# Test_Board.net
KiCad netlist of a schematic drawn in Altium Designer
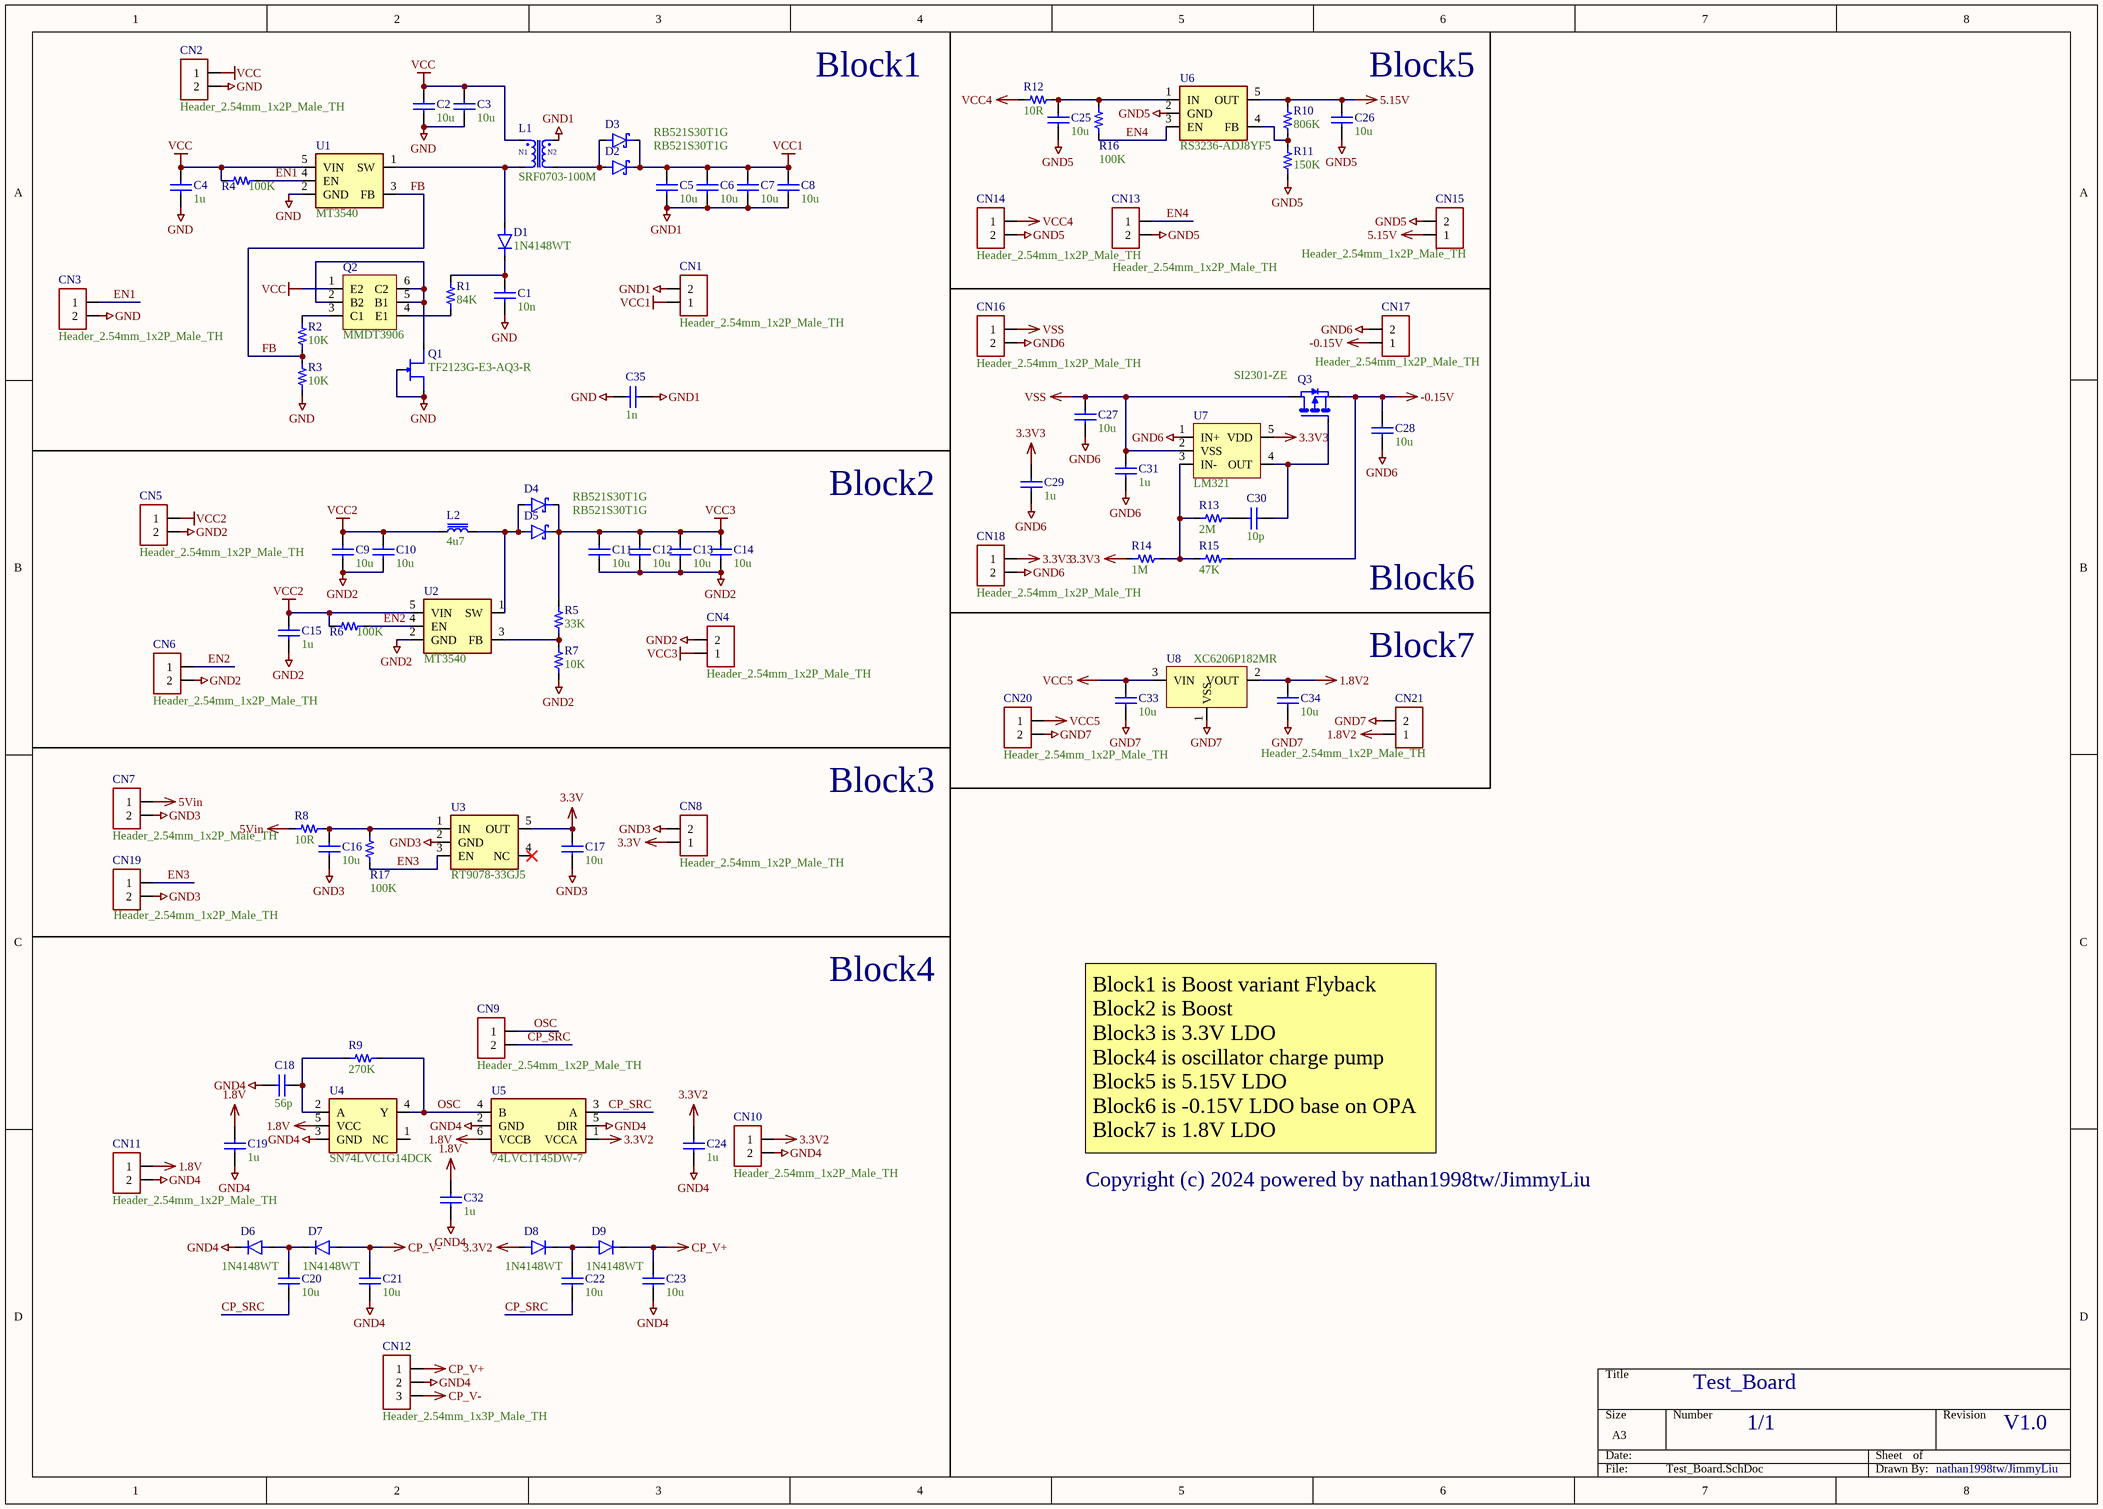
[diagram p0: Test_Board.SchDoc]

(export (version "E")
  (design (tool "Eeschema 10.0.6"))
  (components
    (comp (ref "C1")
      (value "10n")
      (footprint "CAP_0402")
      (description "Capacitor")
      (fields (field (name "VOLTAGE") "V"))
      (libsource (lib "Passive") (part "Capacitor"))
    )
    (comp (ref "C2")
      (value "10u")
      (footprint "CAP_0603")
      (description "Capacitor")
      (fields (field (name "VOLTAGE") "V"))
      (libsource (lib "Passive") (part "Capacitor"))
    )
    (comp (ref "C3")
      (value "10u")
      (footprint "CAP_0603")
      (description "Capacitor")
      (fields (field (name "VOLTAGE") "V"))
      (libsource (lib "Passive") (part "Capacitor"))
    )
    (comp (ref "C4")
      (value "1u")
      (footprint "CAP_0402")
      (description "Capacitor")
      (fields (field (name "VOLTAGE") "V"))
      (libsource (lib "Passive") (part "Capacitor"))
    )
    (comp (ref "C5")
      (value "10u")
      (footprint "CAP_0603")
      (description "Capacitor")
      (fields (field (name "VOLTAGE") "V"))
      (libsource (lib "Passive") (part "Capacitor"))
    )
    (comp (ref "C6")
      (value "10u")
      (footprint "CAP_0603")
      (description "Capacitor")
      (fields (field (name "VOLTAGE") "V"))
      (libsource (lib "Passive") (part "Capacitor"))
    )
    (comp (ref "C7")
      (value "10u")
      (footprint "CAP_0603")
      (description "Capacitor")
      (fields (field (name "VOLTAGE") "V"))
      (libsource (lib "Passive") (part "Capacitor"))
    )
    (comp (ref "C8")
      (value "10u")
      (footprint "CAP_0603")
      (description "Capacitor")
      (fields (field (name "VOLTAGE") "V"))
      (libsource (lib "Passive") (part "Capacitor"))
    )
    (comp (ref "C9")
      (value "10u")
      (footprint "CAP_0603")
      (description "Capacitor")
      (fields (field (name "VOLTAGE") "V"))
      (libsource (lib "Passive") (part "Capacitor"))
    )
    (comp (ref "C10")
      (value "10u")
      (footprint "CAP_0603")
      (description "Capacitor")
      (fields (field (name "VOLTAGE") "V"))
      (libsource (lib "Passive") (part "Capacitor"))
    )
    (comp (ref "C11")
      (value "10u")
      (footprint "CAP_0603")
      (description "Capacitor")
      (fields (field (name "VOLTAGE") "V"))
      (libsource (lib "Passive") (part "Capacitor"))
    )
    (comp (ref "C12")
      (value "10u")
      (footprint "CAP_0603")
      (description "Capacitor")
      (fields (field (name "VOLTAGE") "V"))
      (libsource (lib "Passive") (part "Capacitor"))
    )
    (comp (ref "C13")
      (value "10u")
      (footprint "CAP_0603")
      (description "Capacitor")
      (fields (field (name "VOLTAGE") "V"))
      (libsource (lib "Passive") (part "Capacitor"))
    )
    (comp (ref "C14")
      (value "10u")
      (footprint "CAP_0603")
      (description "Capacitor")
      (fields (field (name "VOLTAGE") "V"))
      (libsource (lib "Passive") (part "Capacitor"))
    )
    (comp (ref "C15")
      (value "1u")
      (footprint "CAP_0402")
      (description "Capacitor")
      (fields (field (name "VOLTAGE") "V"))
      (libsource (lib "Passive") (part "Capacitor"))
    )
    (comp (ref "C16")
      (value "10u")
      (footprint "CAP_0603")
      (description "Capacitor")
      (fields (field (name "VOLTAGE") "V"))
      (libsource (lib "Passive") (part "Capacitor"))
    )
    (comp (ref "C17")
      (value "10u")
      (footprint "CAP_0603")
      (description "Capacitor")
      (fields (field (name "VOLTAGE") "V"))
      (libsource (lib "Passive") (part "Capacitor"))
    )
    (comp (ref "C18")
      (value "56p")
      (footprint "CAP_0402")
      (description "Capacitor")
      (fields (field (name "VOLTAGE") "V"))
      (libsource (lib "Passive") (part "Capacitor"))
    )
    (comp (ref "C19")
      (value "1u")
      (footprint "CAP_0402")
      (description "Capacitor")
      (fields (field (name "VOLTAGE") "V"))
      (libsource (lib "Passive") (part "Capacitor"))
    )
    (comp (ref "C20")
      (value "10u")
      (footprint "CAP_0402")
      (description "Capacitor")
      (fields (field (name "VOLTAGE") "V"))
      (libsource (lib "Passive") (part "Capacitor"))
    )
    (comp (ref "C21")
      (value "10u")
      (footprint "CAP_0402")
      (description "Capacitor")
      (fields (field (name "VOLTAGE") "V"))
      (libsource (lib "Passive") (part "Capacitor"))
    )
    (comp (ref "C22")
      (value "10u")
      (footprint "CAP_0402")
      (description "Capacitor")
      (fields (field (name "VOLTAGE") "V"))
      (libsource (lib "Passive") (part "Capacitor"))
    )
    (comp (ref "C23")
      (value "10u")
      (footprint "CAP_0402")
      (description "Capacitor")
      (fields (field (name "VOLTAGE") "V"))
      (libsource (lib "Passive") (part "Capacitor"))
    )
    (comp (ref "C24")
      (value "1u")
      (footprint "CAP_0402")
      (description "Capacitor")
      (fields (field (name "VOLTAGE") "V"))
      (libsource (lib "Passive") (part "Capacitor"))
    )
    (comp (ref "C25")
      (value "10u")
      (footprint "CAP_0603")
      (description "Capacitor")
      (fields (field (name "VOLTAGE") "V"))
      (libsource (lib "Passive") (part "Capacitor"))
    )
    (comp (ref "C26")
      (value "10u")
      (footprint "CAP_0603")
      (description "Capacitor")
      (fields (field (name "VOLTAGE") "V"))
      (libsource (lib "Passive") (part "Capacitor"))
    )
    (comp (ref "C27")
      (value "10u")
      (footprint "CAP_0603")
      (description "Capacitor")
      (fields (field (name "VOLTAGE") "V"))
      (libsource (lib "Passive") (part "Capacitor"))
    )
    (comp (ref "C28")
      (value "10u")
      (footprint "CAP_0402")
      (description "Capacitor")
      (fields (field (name "VOLTAGE") "V"))
      (libsource (lib "Passive") (part "Capacitor"))
    )
    (comp (ref "C29")
      (value "1u")
      (footprint "CAP_0402")
      (description "Capacitor")
      (fields (field (name "VOLTAGE") "V"))
      (libsource (lib "Passive") (part "Capacitor"))
    )
    (comp (ref "C30")
      (value "10p")
      (footprint "CAP_0402")
      (description "Capacitor")
      (fields (field (name "VOLTAGE") "V"))
      (libsource (lib "Passive") (part "Capacitor"))
    )
    (comp (ref "C31")
      (value "1u")
      (footprint "CAP_0402")
      (description "Capacitor")
      (fields (field (name "VOLTAGE") "V"))
      (libsource (lib "Passive") (part "Capacitor"))
    )
    (comp (ref "C32")
      (value "1u")
      (footprint "CAP_0402")
      (description "Capacitor")
      (fields (field (name "VOLTAGE") "V"))
      (libsource (lib "Passive") (part "Capacitor"))
    )
    (comp (ref "C33")
      (value "10u")
      (footprint "CAP_0603")
      (description "Capacitor")
      (fields (field (name "VOLTAGE") "V"))
      (libsource (lib "Passive") (part "Capacitor"))
    )
    (comp (ref "C34")
      (value "10u")
      (footprint "CAP_0603")
      (description "Capacitor")
      (fields (field (name "VOLTAGE") "V"))
      (libsource (lib "Passive") (part "Capacitor"))
    )
    (comp (ref "C35")
      (value "1n")
      (footprint "CAP_0402")
      (description "Capacitor")
      (fields (field (name "VOLTAGE") "V"))
      (libsource (lib "Passive") (part "Capacitor"))
    )
    (comp (ref "CN1")
      (value "Header_2.54mm_1x2P_Male_TH")
      (footprint "Header_2.54mm_1x2P_Male_TH")
      (description "Header_2.54mm_1x2P_Male\r\nThrough-hole")
      (libsource (lib "Connector") (part "Header_2.54mm_1x2P_Male_TH"))
    )
    (comp (ref "CN2")
      (value "Header_2.54mm_1x2P_Male_TH")
      (footprint "Header_2.54mm_1x2P_Male_TH")
      (description "Header_2.54mm_1x2P_Male\r\nThrough-hole")
      (libsource (lib "Connector") (part "Header_2.54mm_1x2P_Male_TH"))
    )
    (comp (ref "CN3")
      (value "Header_2.54mm_1x2P_Male_TH")
      (footprint "Header_2.54mm_1x2P_Male_TH")
      (description "Header_2.54mm_1x2P_Male\r\nThrough-hole")
      (libsource (lib "Connector") (part "Header_2.54mm_1x2P_Male_TH"))
    )
    (comp (ref "CN4")
      (value "Header_2.54mm_1x2P_Male_TH")
      (footprint "Header_2.54mm_1x2P_Male_TH")
      (description "Header_2.54mm_1x2P_Male\r\nThrough-hole")
      (libsource (lib "Connector") (part "Header_2.54mm_1x2P_Male_TH"))
    )
    (comp (ref "CN5")
      (value "Header_2.54mm_1x2P_Male_TH")
      (footprint "Header_2.54mm_1x2P_Male_TH")
      (description "Header_2.54mm_1x2P_Male\r\nThrough-hole")
      (libsource (lib "Connector") (part "Header_2.54mm_1x2P_Male_TH"))
    )
    (comp (ref "CN6")
      (value "Header_2.54mm_1x2P_Male_TH")
      (footprint "Header_2.54mm_1x2P_Male_TH")
      (description "Header_2.54mm_1x2P_Male\r\nThrough-hole")
      (libsource (lib "Connector") (part "Header_2.54mm_1x2P_Male_TH"))
    )
    (comp (ref "CN7")
      (value "Header_2.54mm_1x2P_Male_TH")
      (footprint "Header_2.54mm_1x2P_Male_TH")
      (description "Header_2.54mm_1x2P_Male\r\nThrough-hole")
      (libsource (lib "Connector") (part "Header_2.54mm_1x2P_Male_TH"))
    )
    (comp (ref "CN8")
      (value "Header_2.54mm_1x2P_Male_TH")
      (footprint "Header_2.54mm_1x2P_Male_TH")
      (description "Header_2.54mm_1x2P_Male\r\nThrough-hole")
      (libsource (lib "Connector") (part "Header_2.54mm_1x2P_Male_TH"))
    )
    (comp (ref "CN9")
      (value "Header_2.54mm_1x2P_Male_TH")
      (footprint "Header_2.54mm_1x2P_Male_TH")
      (description "Header_2.54mm_1x2P_Male\r\nThrough-hole")
      (libsource (lib "Connector") (part "Header_2.54mm_1x2P_Male_TH"))
    )
    (comp (ref "CN10")
      (value "Header_2.54mm_1x2P_Male_TH")
      (footprint "Header_2.54mm_1x2P_Male_TH")
      (description "Header_2.54mm_1x2P_Male\r\nThrough-hole")
      (libsource (lib "Connector") (part "Header_2.54mm_1x2P_Male_TH"))
    )
    (comp (ref "CN11")
      (value "Header_2.54mm_1x2P_Male_TH")
      (footprint "Header_2.54mm_1x2P_Male_TH")
      (description "Header_2.54mm_1x2P_Male\r\nThrough-hole")
      (libsource (lib "Connector") (part "Header_2.54mm_1x2P_Male_TH"))
    )
    (comp (ref "CN12")
      (value "Header_2.54mm_1x3P_Male_TH")
      (footprint "Header_2.54mm_1x3P_Male_TH")
      (description "Header_2.54mm_1x3P_Male\r\nThrough-hole")
      (libsource (lib "Connector") (part "Header_2.54mm_1x3P_Male_TH"))
    )
    (comp (ref "CN13")
      (value "Header_2.54mm_1x2P_Male_TH")
      (footprint "Header_2.54mm_1x2P_Male_TH")
      (description "Header_2.54mm_1x2P_Male\r\nThrough-hole")
      (libsource (lib "Connector") (part "Header_2.54mm_1x2P_Male_TH"))
    )
    (comp (ref "CN14")
      (value "Header_2.54mm_1x2P_Male_TH")
      (footprint "Header_2.54mm_1x2P_Male_TH")
      (description "Header_2.54mm_1x2P_Male\r\nThrough-hole")
      (libsource (lib "Connector") (part "Header_2.54mm_1x2P_Male_TH"))
    )
    (comp (ref "CN15")
      (value "Header_2.54mm_1x2P_Male_TH")
      (footprint "Header_2.54mm_1x2P_Male_TH")
      (description "Header_2.54mm_1x2P_Male\r\nThrough-hole")
      (libsource (lib "Connector") (part "Header_2.54mm_1x2P_Male_TH"))
    )
    (comp (ref "CN16")
      (value "Header_2.54mm_1x2P_Male_TH")
      (footprint "Header_2.54mm_1x2P_Male_TH")
      (description "Header_2.54mm_1x2P_Male\r\nThrough-hole")
      (libsource (lib "Connector") (part "Header_2.54mm_1x2P_Male_TH"))
    )
    (comp (ref "CN17")
      (value "Header_2.54mm_1x2P_Male_TH")
      (footprint "Header_2.54mm_1x2P_Male_TH")
      (description "Header_2.54mm_1x2P_Male\r\nThrough-hole")
      (libsource (lib "Connector") (part "Header_2.54mm_1x2P_Male_TH"))
    )
    (comp (ref "CN18")
      (value "Header_2.54mm_1x2P_Male_TH")
      (footprint "Header_2.54mm_1x2P_Male_TH")
      (description "Header_2.54mm_1x2P_Male\r\nThrough-hole")
      (libsource (lib "Connector") (part "Header_2.54mm_1x2P_Male_TH"))
    )
    (comp (ref "CN19")
      (value "Header_2.54mm_1x2P_Male_TH")
      (footprint "Header_2.54mm_1x2P_Male_TH")
      (description "Header_2.54mm_1x2P_Male\r\nThrough-hole")
      (libsource (lib "Connector") (part "Header_2.54mm_1x2P_Male_TH"))
    )
    (comp (ref "CN20")
      (value "Header_2.54mm_1x2P_Male_TH")
      (footprint "Header_2.54mm_1x2P_Male_TH")
      (description "Header_2.54mm_1x2P_Male\r\nThrough-hole")
      (libsource (lib "Connector") (part "Header_2.54mm_1x2P_Male_TH"))
    )
    (comp (ref "CN21")
      (value "Header_2.54mm_1x2P_Male_TH")
      (footprint "Header_2.54mm_1x2P_Male_TH")
      (description "Header_2.54mm_1x2P_Male\r\nThrough-hole")
      (libsource (lib "Connector") (part "Header_2.54mm_1x2P_Male_TH"))
    )
    (comp (ref "D1")
      (value "1N4148WT")
      (footprint "SOD-523-2")
      (description "Signal Diode")
      (libsource (lib "Diode") (part "1N4148WT"))
    )
    (comp (ref "D2")
      (value "RB521S30T1G")
      (footprint "SOD-523-2")
      (description "Schottky Diode")
      (libsource (lib "Diode") (part "RB521S30T1G"))
    )
    (comp (ref "D3")
      (value "RB521S30T1G")
      (footprint "SOD-523-2")
      (description "Schottky Diode")
      (libsource (lib "Diode") (part "RB521S30T1G"))
    )
    (comp (ref "D4")
      (value "RB521S30T1G")
      (footprint "SOD-523-2")
      (description "Schottky Diode")
      (libsource (lib "Diode") (part "RB521S30T1G"))
    )
    (comp (ref "D5")
      (value "RB521S30T1G")
      (footprint "SOD-523-2")
      (description "Schottky Diode")
      (libsource (lib "Diode") (part "RB521S30T1G"))
    )
    (comp (ref "D6")
      (value "1N4148WT")
      (footprint "SOD-523-2")
      (description "Signal Diode")
      (libsource (lib "Diode") (part "1N4148WT"))
    )
    (comp (ref "D7")
      (value "1N4148WT")
      (footprint "SOD-523-2")
      (description "Signal Diode")
      (libsource (lib "Diode") (part "1N4148WT"))
    )
    (comp (ref "D8")
      (value "1N4148WT")
      (footprint "SOD-523-2")
      (description "Signal Diode")
      (libsource (lib "Diode") (part "1N4148WT"))
    )
    (comp (ref "D9")
      (value "1N4148WT")
      (footprint "SOD-523-2")
      (description "Signal Diode")
      (libsource (lib "Diode") (part "1N4148WT"))
    )
    (comp (ref "L1")
      (value "SRF0703-100M")
      (footprint "SRF0703")
      (libsource (lib "Passive") (part "SRF0703-100M"))
    )
    (comp (ref "L2")
      (value "4u7")
      (footprint "IND_0806")
      (description "Inductor_IRON")
      (libsource (lib "Passive") (part "Inductor_IRON"))
    )
    (comp (ref "Q1")
      (value "TF2123G-E3-AQ3-R")
      (footprint "SOT-723-3_120X80X50_40P")
      (description "N-JFET")
      (libsource (lib "Transistor") (part "TF2123G-E3-AQ3-R"))
    )
    (comp (ref "Q2")
      (value "MMDT3906")
      (footprint "SOT-363-6_215X130X110_65P")
      (description "Double PNP")
      (libsource (lib "Transistor") (part "MMDT3906"))
    )
    (comp (ref "Q3")
      (value "SI2301-ZE")
      (footprint "SOT-23-3_290X130X103_95P")
      (description "P-MOSFET")
      (libsource (lib "Transistor") (part "SI2301-ZE"))
    )
    (comp (ref "R1")
      (value "84K")
      (footprint "RES_0402")
      (description "Resistor")
      (fields (field (name "VOLTAGE") "V"))
      (libsource (lib "Passive") (part "Resistor"))
    )
    (comp (ref "R2")
      (value "10K")
      (footprint "RES_0402")
      (description "Resistor")
      (fields (field (name "VOLTAGE") "V"))
      (libsource (lib "Passive") (part "Resistor"))
    )
    (comp (ref "R3")
      (value "10K")
      (footprint "RES_0402")
      (description "Resistor")
      (fields (field (name "VOLTAGE") "V"))
      (libsource (lib "Passive") (part "Resistor"))
    )
    (comp (ref "R4")
      (value "100K")
      (footprint "RES_0402")
      (description "Resistor")
      (fields (field (name "VOLTAGE") "V"))
      (libsource (lib "Passive") (part "Resistor"))
    )
    (comp (ref "R5")
      (value "33K")
      (footprint "RES_0402")
      (description "Resistor")
      (fields (field (name "VOLTAGE") "V"))
      (libsource (lib "Passive") (part "Resistor"))
    )
    (comp (ref "R6")
      (value "100K")
      (footprint "RES_0402")
      (description "Resistor")
      (fields (field (name "VOLTAGE") "V"))
      (libsource (lib "Passive") (part "Resistor"))
    )
    (comp (ref "R7")
      (value "10K")
      (footprint "RES_0402")
      (description "Resistor")
      (fields (field (name "VOLTAGE") "V"))
      (libsource (lib "Passive") (part "Resistor"))
    )
    (comp (ref "R8")
      (value "10R")
      (footprint "RES_0402")
      (description "Resistor")
      (fields (field (name "VOLTAGE") "V"))
      (libsource (lib "Passive") (part "Resistor"))
    )
    (comp (ref "R9")
      (value "270K")
      (footprint "RES_0402")
      (description "Resistor")
      (fields (field (name "VOLTAGE") "V"))
      (libsource (lib "Passive") (part "Resistor"))
    )
    (comp (ref "R10")
      (value "806K")
      (footprint "RES_0402")
      (description "Resistor")
      (fields (field (name "VOLTAGE") "V"))
      (libsource (lib "Passive") (part "Resistor"))
    )
    (comp (ref "R11")
      (value "150K")
      (footprint "RES_0402")
      (description "Resistor")
      (fields (field (name "VOLTAGE") "V"))
      (libsource (lib "Passive") (part "Resistor"))
    )
    (comp (ref "R12")
      (value "10R")
      (footprint "RES_0402")
      (description "Resistor")
      (fields (field (name "VOLTAGE") "V"))
      (libsource (lib "Passive") (part "Resistor"))
    )
    (comp (ref "R13")
      (value "2M")
      (footprint "RES_0402")
      (description "Resistor")
      (fields (field (name "VOLTAGE") "V"))
      (libsource (lib "Passive") (part "Resistor"))
    )
    (comp (ref "R14")
      (value "1M")
      (footprint "RES_0402")
      (description "Resistor")
      (fields (field (name "VOLTAGE") "V"))
      (libsource (lib "Passive") (part "Resistor"))
    )
    (comp (ref "R15")
      (value "47K")
      (footprint "RES_0402")
      (description "Resistor")
      (fields (field (name "VOLTAGE") "V"))
      (libsource (lib "Passive") (part "Resistor"))
    )
    (comp (ref "R16")
      (value "100K")
      (footprint "RES_0402")
      (description "Resistor")
      (fields (field (name "VOLTAGE") "V"))
      (libsource (lib "Passive") (part "Resistor"))
    )
    (comp (ref "R17")
      (value "100K")
      (footprint "RES_0402")
      (description "Resistor")
      (fields (field (name "VOLTAGE") "V"))
      (libsource (lib "Passive") (part "Resistor"))
    )
    (comp (ref "U1")
      (value "MT3540")
      (footprint "SOT-23-5_290X160X120_95P")
      (description "Asynchronous Boost Convertor\r\nVin:2.5~5.5V\r\nVout:Vin~28V")
      (libsource (lib "IC") (part "MT3540"))
    )
    (comp (ref "U2")
      (value "MT3540")
      (footprint "SOT-23-5_290X160X120_95P")
      (description "Asynchronous Boost Convertor\r\nVin:2.5~5.5V\r\nVout:Vin~28V")
      (libsource (lib "IC") (part "MT3540"))
    )
    (comp (ref "U3")
      (value "RT9078-33GJ5")
      (footprint "SOT-23-5_290X160X120_95P")
      (description "LDO 3.3V")
      (libsource (lib "IC") (part "RT9078-33GJ5"))
    )
    (comp (ref "U4")
      (value "SN74LVC1G14DCK")
      (footprint "SOT-353-5_215X130X110_65P")
      (description "Schmitt trigger inverter")
      (libsource (lib "IC") (part "SN74LVC1G14DCK"))
    )
    (comp (ref "U5")
      (value "74LVC1T45DW-7")
      (footprint "SOT-363-6_215X130X110_65P")
      (description "1-bit Voltage Translator")
      (libsource (lib "IC") (part "74LVC1T45DW-7"))
    )
    (comp (ref "U6")
      (value "RS3236-ADJ8YF5")
      (footprint "SOT-23-5_290X160X120_95P")
      (description "LDO Adjustable")
      (libsource (lib "IC") (part "RS3236-ADJ8YF5"))
    )
    (comp (ref "U7")
      (value "LM321")
      (footprint "SOT-23-5_290X160X120_95P")
      (description "Single_OPA")
      (libsource (lib "IC") (part "LM321"))
    )
    (comp (ref "U8")
      (value "XC6206P182MR")
      (footprint "SOT-23-3_290X130X95_95P_S")
      (description "LDO 1.8V")
      (libsource (lib "IC") (part "XC6206P182MR"))
    )
  )
  (nets
    (net (code "1") (name "-0.15V") (class "Default")
      (node (ref "C28") (pin "1") (pintype "passive"))
      (node (ref "CN17") (pin "1") (pinfunction "1_1") (pintype "passive"))
      (node (ref "Q3") (pin "2") (pinfunction "S_2") (pintype "passive"))
      (node (ref "R15") (pin "1") (pinfunction "1_1") (pintype "passive"))
    )
    (net (code "2") (name "/CP_SRC") (class "Default")
      (node (ref "C20") (pin "2") (pintype "passive"))
      (node (ref "C22") (pin "2") (pintype "passive"))
      (node (ref "CN9") (pin "2") (pinfunction "2_2") (pintype "passive"))
      (node (ref "U5") (pin "3") (pinfunction "A_3") (pintype "passive"))
    )
    (net (code "3") (name "/EN1") (class "Default")
      (node (ref "CN3") (pin "1") (pinfunction "1_1") (pintype "passive"))
      (node (ref "R4") (pin "1") (pinfunction "1_1") (pintype "passive"))
      (node (ref "U1") (pin "4") (pinfunction "EN_4") (pintype "passive"))
    )
    (net (code "4") (name "/EN2") (class "Default")
      (node (ref "CN6") (pin "1") (pinfunction "1_1") (pintype "passive"))
      (node (ref "R6") (pin "1") (pinfunction "1_1") (pintype "passive"))
      (node (ref "U2") (pin "4") (pinfunction "EN_4") (pintype "passive"))
    )
    (net (code "5") (name "/EN3") (class "Default")
      (node (ref "CN19") (pin "1") (pinfunction "1_1") (pintype "passive"))
      (node (ref "R17") (pin "2") (pinfunction "2_2") (pintype "passive"))
      (node (ref "U3") (pin "3") (pinfunction "EN_3") (pintype "passive"))
    )
    (net (code "6") (name "/EN4") (class "Default")
      (node (ref "CN13") (pin "1") (pinfunction "1_1") (pintype "passive"))
      (node (ref "R16") (pin "1") (pinfunction "1_1") (pintype "passive"))
      (node (ref "U6") (pin "3") (pinfunction "EN_3") (pintype "passive"))
    )
    (net (code "7") (name "/FB") (class "Default")
      (node (ref "R2") (pin "1") (pinfunction "1_1") (pintype "passive"))
      (node (ref "R3") (pin "2") (pinfunction "2_2") (pintype "passive"))
      (node (ref "U1") (pin "3") (pinfunction "FB_3") (pintype "passive"))
    )
    (net (code "8") (name "/OSC") (class "Default")
      (node (ref "CN9") (pin "1") (pinfunction "1_1") (pintype "passive"))
      (node (ref "R9") (pin "1") (pinfunction "1_1") (pintype "passive"))
      (node (ref "U4") (pin "4") (pinfunction "Y_4") (pintype "passive"))
      (node (ref "U5") (pin "4") (pinfunction "B_4") (pintype "passive"))
    )
    (net (code "9") (name "1.8V") (class "Default")
      (node (ref "C19") (pin "1") (pintype "passive"))
      (node (ref "C32") (pin "1") (pintype "passive"))
      (node (ref "CN11") (pin "1") (pinfunction "1_1") (pintype "passive"))
      (node (ref "U4") (pin "5") (pinfunction "VCC_5") (pintype "passive"))
      (node (ref "U5") (pin "6") (pinfunction "VCCB_6") (pintype "passive"))
    )
    (net (code "10") (name "1.8V2") (class "Default")
      (node (ref "C34") (pin "1") (pintype "passive"))
      (node (ref "CN21") (pin "1") (pinfunction "1_1") (pintype "passive"))
      (node (ref "U8") (pin "2") (pinfunction "VOUT_2") (pintype "passive"))
    )
    (net (code "11") (name "3.3V") (class "Default")
      (node (ref "C17") (pin "1") (pintype "passive"))
      (node (ref "CN8") (pin "1") (pinfunction "1_1") (pintype "passive"))
      (node (ref "U3") (pin "5") (pinfunction "OUT_5") (pintype "passive"))
    )
    (net (code "12") (name "3.3V2") (class "Default")
      (node (ref "C24") (pin "1") (pintype "passive"))
      (node (ref "CN10") (pin "1") (pinfunction "1_1") (pintype "passive"))
      (node (ref "D8") (pin "2") (pinfunction "A_2") (pintype "passive"))
      (node (ref "U5") (pin "1") (pinfunction "VCCA_1") (pintype "passive"))
    )
    (net (code "13") (name "3.3V3") (class "Default")
      (node (ref "C29") (pin "1") (pintype "passive"))
      (node (ref "CN18") (pin "1") (pinfunction "1_1") (pintype "passive"))
      (node (ref "R14") (pin "2") (pinfunction "2_2") (pintype "passive"))
      (node (ref "U7") (pin "5") (pinfunction "VDD_5") (pintype "power_in"))
    )
    (net (code "14") (name "5.15V") (class "Default")
      (node (ref "C26") (pin "1") (pintype "passive"))
      (node (ref "CN15") (pin "1") (pinfunction "1_1") (pintype "passive"))
      (node (ref "R10") (pin "2") (pinfunction "2_2") (pintype "passive"))
      (node (ref "U6") (pin "5") (pinfunction "OUT_5") (pintype "passive"))
    )
    (net (code "15") (name "5Vin") (class "Default")
      (node (ref "CN7") (pin "1") (pinfunction "1_1") (pintype "passive"))
      (node (ref "R8") (pin "2") (pinfunction "2_2") (pintype "passive"))
    )
    (net (code "16") (name "CP_V+") (class "Default")
      (node (ref "C23") (pin "1") (pintype "passive"))
      (node (ref "CN12") (pin "1") (pinfunction "1_1") (pintype "passive"))
      (node (ref "D9") (pin "1") (pinfunction "K_1") (pintype "passive"))
    )
    (net (code "17") (name "CP_V-") (class "Default")
      (node (ref "C21") (pin "1") (pintype "passive"))
      (node (ref "CN12") (pin "3") (pinfunction "3_3") (pintype "passive"))
      (node (ref "D7") (pin "2") (pinfunction "A_2") (pintype "passive"))
    )
    (net (code "18") (name "GND") (class "Default")
      (node (ref "C1") (pin "2") (pintype "passive"))
      (node (ref "C2") (pin "2") (pintype "passive"))
      (node (ref "C3") (pin "2") (pintype "passive"))
      (node (ref "C35") (pin "1") (pintype "passive"))
      (node (ref "C4") (pin "2") (pintype "passive"))
      (node (ref "CN2") (pin "2") (pinfunction "2_2") (pintype "passive"))
      (node (ref "CN3") (pin "2") (pinfunction "2_2") (pintype "passive"))
      (node (ref "Q1") (pin "2") (pinfunction "S_2") (pintype "passive"))
      (node (ref "Q1") (pin "3") (pinfunction "G_3") (pintype "passive"))
      (node (ref "R3") (pin "1") (pinfunction "1_1") (pintype "passive"))
      (node (ref "U1") (pin "2") (pinfunction "GND_2") (pintype "passive"))
    )
    (net (code "19") (name "GND1") (class "Default")
      (node (ref "C35") (pin "2") (pintype "passive"))
      (node (ref "C5") (pin "2") (pintype "passive"))
      (node (ref "C6") (pin "2") (pintype "passive"))
      (node (ref "C7") (pin "2") (pintype "passive"))
      (node (ref "C8") (pin "2") (pintype "passive"))
      (node (ref "CN1") (pin "2") (pinfunction "2_2") (pintype "passive"))
      (node (ref "L1") (pin "2") (pinfunction "2_2") (pintype "passive"))
    )
    (net (code "20") (name "GND2") (class "Default")
      (node (ref "C10") (pin "2") (pintype "passive"))
      (node (ref "C11") (pin "2") (pintype "passive"))
      (node (ref "C12") (pin "2") (pintype "passive"))
      (node (ref "C13") (pin "2") (pintype "passive"))
      (node (ref "C14") (pin "2") (pintype "passive"))
      (node (ref "C15") (pin "2") (pintype "passive"))
      (node (ref "C9") (pin "2") (pintype "passive"))
      (node (ref "CN4") (pin "2") (pinfunction "2_2") (pintype "passive"))
      (node (ref "CN5") (pin "2") (pinfunction "2_2") (pintype "passive"))
      (node (ref "CN6") (pin "2") (pinfunction "2_2") (pintype "passive"))
      (node (ref "R7") (pin "1") (pinfunction "1_1") (pintype "passive"))
      (node (ref "U2") (pin "2") (pinfunction "GND_2") (pintype "passive"))
    )
    (net (code "21") (name "GND3") (class "Default")
      (node (ref "C16") (pin "2") (pintype "passive"))
      (node (ref "C17") (pin "2") (pintype "passive"))
      (node (ref "CN19") (pin "2") (pinfunction "2_2") (pintype "passive"))
      (node (ref "CN7") (pin "2") (pinfunction "2_2") (pintype "passive"))
      (node (ref "CN8") (pin "2") (pinfunction "2_2") (pintype "passive"))
      (node (ref "U3") (pin "2") (pinfunction "GND_2") (pintype "passive"))
    )
    (net (code "22") (name "GND4") (class "Default")
      (node (ref "C18") (pin "2") (pintype "passive"))
      (node (ref "C19") (pin "2") (pintype "passive"))
      (node (ref "C21") (pin "2") (pintype "passive"))
      (node (ref "C23") (pin "2") (pintype "passive"))
      (node (ref "C24") (pin "2") (pintype "passive"))
      (node (ref "C32") (pin "2") (pintype "passive"))
      (node (ref "CN10") (pin "2") (pinfunction "2_2") (pintype "passive"))
      (node (ref "CN11") (pin "2") (pinfunction "2_2") (pintype "passive"))
      (node (ref "CN12") (pin "2") (pinfunction "2_2") (pintype "passive"))
      (node (ref "D6") (pin "1") (pinfunction "K_1") (pintype "passive"))
      (node (ref "U4") (pin "3") (pinfunction "GND_3") (pintype "passive"))
      (node (ref "U5") (pin "2") (pinfunction "GND_2") (pintype "passive"))
      (node (ref "U5") (pin "5") (pinfunction "DIR_5") (pintype "passive"))
    )
    (net (code "23") (name "GND5") (class "Default")
      (node (ref "C25") (pin "2") (pintype "passive"))
      (node (ref "C26") (pin "2") (pintype "passive"))
      (node (ref "CN13") (pin "2") (pinfunction "2_2") (pintype "passive"))
      (node (ref "CN14") (pin "2") (pinfunction "2_2") (pintype "passive"))
      (node (ref "CN15") (pin "2") (pinfunction "2_2") (pintype "passive"))
      (node (ref "R11") (pin "1") (pinfunction "1_1") (pintype "passive"))
      (node (ref "U6") (pin "2") (pinfunction "GND_2") (pintype "passive"))
    )
    (net (code "24") (name "GND6") (class "Default")
      (node (ref "C27") (pin "2") (pintype "passive"))
      (node (ref "C28") (pin "2") (pintype "passive"))
      (node (ref "C29") (pin "2") (pintype "passive"))
      (node (ref "C31") (pin "2") (pintype "passive"))
      (node (ref "CN16") (pin "2") (pinfunction "2_2") (pintype "passive"))
      (node (ref "CN17") (pin "2") (pinfunction "2_2") (pintype "passive"))
      (node (ref "CN18") (pin "2") (pinfunction "2_2") (pintype "passive"))
      (node (ref "U7") (pin "1") (pinfunction "IN+_1") (pintype "power_in"))
    )
    (net (code "25") (name "GND7") (class "Default")
      (node (ref "C33") (pin "2") (pintype "passive"))
      (node (ref "C34") (pin "2") (pintype "passive"))
      (node (ref "CN20") (pin "2") (pinfunction "2_2") (pintype "passive"))
      (node (ref "CN21") (pin "2") (pinfunction "2_2") (pintype "passive"))
      (node (ref "U8") (pin "1") (pinfunction "VSS_1") (pintype "passive"))
    )
    (net (code "26") (name "Net-(C30-Pad1)") (class "Default")
      (node (ref "C30") (pin "1") (pintype "passive"))
      (node (ref "R13") (pin "1") (pinfunction "1_1") (pintype "passive"))
    )
    (net (code "27") (name "Net-(D1-A)") (class "Default")
      (node (ref "D1") (pin "2") (pinfunction "A_2") (pintype "passive"))
      (node (ref "L1") (pin "3") (pinfunction "3_3") (pintype "passive"))
      (node (ref "U1") (pin "1") (pinfunction "SW_1") (pintype "passive"))
    )
    (net (code "28") (name "Net-(D1-K)") (class "Default")
      (node (ref "C1") (pin "1") (pintype "passive"))
      (node (ref "D1") (pin "1") (pinfunction "K_1") (pintype "passive"))
      (node (ref "R1") (pin "2") (pinfunction "2_2") (pintype "passive"))
    )
    (net (code "29") (name "Net-(D2-A)") (class "Default")
      (node (ref "D2") (pin "2") (pinfunction "A_2") (pintype "passive"))
      (node (ref "D3") (pin "2") (pinfunction "A_2") (pintype "passive"))
      (node (ref "L1") (pin "4") (pinfunction "4_4") (pintype "passive"))
    )
    (net (code "30") (name "Net-(D4-A)") (class "Default")
      (node (ref "D4") (pin "2") (pinfunction "A_2") (pintype "passive"))
      (node (ref "D5") (pin "2") (pinfunction "A_2") (pintype "passive"))
      (node (ref "L2") (pin "2") (pinfunction "2_2") (pintype "passive"))
      (node (ref "U2") (pin "1") (pinfunction "SW_1") (pintype "passive"))
    )
    (net (code "31") (name "Net-(D6-A)") (class "Default")
      (node (ref "C20") (pin "1") (pintype "passive"))
      (node (ref "D6") (pin "2") (pinfunction "A_2") (pintype "passive"))
      (node (ref "D7") (pin "1") (pinfunction "K_1") (pintype "passive"))
    )
    (net (code "32") (name "Net-(D8-K)") (class "Default")
      (node (ref "C22") (pin "1") (pintype "passive"))
      (node (ref "D8") (pin "1") (pinfunction "K_1") (pintype "passive"))
      (node (ref "D9") (pin "2") (pinfunction "A_2") (pintype "passive"))
    )
    (net (code "33") (name "Net-(Q1-D)") (class "Default")
      (node (ref "Q1") (pin "1") (pinfunction "D_1") (pintype "passive"))
      (node (ref "Q2") (pin "2") (pinfunction "B2_2") (pintype "passive"))
      (node (ref "Q2") (pin "5") (pinfunction "B1_5") (pintype "passive"))
      (node (ref "Q2") (pin "6") (pinfunction "C2_6") (pintype "passive"))
    )
    (net (code "34") (name "Net-(Q2-C1)") (class "Default")
      (node (ref "Q2") (pin "3") (pinfunction "C1_3") (pintype "passive"))
      (node (ref "R2") (pin "2") (pinfunction "2_2") (pintype "passive"))
    )
    (net (code "35") (name "Net-(Q2-E1)") (class "Default")
      (node (ref "Q2") (pin "4") (pinfunction "E1_4") (pintype "passive"))
      (node (ref "R1") (pin "1") (pinfunction "1_1") (pintype "passive"))
    )
    (net (code "36") (name "Net-(Q3-G)") (class "Default")
      (node (ref "C30") (pin "2") (pintype "passive"))
      (node (ref "Q3") (pin "1") (pinfunction "G_1") (pintype "passive"))
      (node (ref "U7") (pin "4") (pinfunction "OUT_4") (pintype "power_in"))
    )
    (net (code "37") (name "Net-(U2-FB)") (class "Default")
      (node (ref "R5") (pin "1") (pinfunction "1_1") (pintype "passive"))
      (node (ref "R7") (pin "2") (pinfunction "2_2") (pintype "passive"))
      (node (ref "U2") (pin "3") (pinfunction "FB_3") (pintype "passive"))
    )
    (net (code "38") (name "Net-(U3-IN)") (class "Default")
      (node (ref "C16") (pin "1") (pintype "passive"))
      (node (ref "R17") (pin "1") (pinfunction "1_1") (pintype "passive"))
      (node (ref "R8") (pin "1") (pinfunction "1_1") (pintype "passive"))
      (node (ref "U3") (pin "1") (pinfunction "IN_1") (pintype "passive"))
    )
    (net (code "39") (name "Net-(U4-A)") (class "Default")
      (node (ref "C18") (pin "1") (pintype "passive"))
      (node (ref "R9") (pin "2") (pinfunction "2_2") (pintype "passive"))
      (node (ref "U4") (pin "2") (pinfunction "A_2") (pintype "passive"))
    )
    (net (code "40") (name "Net-(U6-FB)") (class "Default")
      (node (ref "R10") (pin "1") (pinfunction "1_1") (pintype "passive"))
      (node (ref "R11") (pin "2") (pinfunction "2_2") (pintype "passive"))
      (node (ref "U6") (pin "4") (pinfunction "FB_4") (pintype "passive"))
    )
    (net (code "41") (name "Net-(U6-IN)") (class "Default")
      (node (ref "C25") (pin "1") (pintype "passive"))
      (node (ref "R12") (pin "1") (pinfunction "1_1") (pintype "passive"))
      (node (ref "R16") (pin "2") (pinfunction "2_2") (pintype "passive"))
      (node (ref "U6") (pin "1") (pinfunction "IN_1") (pintype "passive"))
    )
    (net (code "42") (name "Net-(U7-IN-)") (class "Default")
      (node (ref "R13") (pin "2") (pinfunction "2_2") (pintype "passive"))
      (node (ref "R14") (pin "1") (pinfunction "1_1") (pintype "passive"))
      (node (ref "R15") (pin "2") (pinfunction "2_2") (pintype "passive"))
      (node (ref "U7") (pin "3") (pinfunction "IN-_3") (pintype "power_in"))
    )
    (net (code "43") (name "VCC") (class "Default")
      (node (ref "C2") (pin "1") (pintype "passive"))
      (node (ref "C3") (pin "1") (pintype "passive"))
      (node (ref "C4") (pin "1") (pintype "passive"))
      (node (ref "CN2") (pin "1") (pinfunction "1_1") (pintype "passive"))
      (node (ref "L1") (pin "1") (pinfunction "1_1") (pintype "passive"))
      (node (ref "Q2") (pin "1") (pinfunction "E2_1") (pintype "passive"))
      (node (ref "R4") (pin "2") (pinfunction "2_2") (pintype "passive"))
      (node (ref "U1") (pin "5") (pinfunction "VIN_5") (pintype "passive"))
    )
    (net (code "44") (name "VCC1") (class "Default")
      (node (ref "C5") (pin "1") (pintype "passive"))
      (node (ref "C6") (pin "1") (pintype "passive"))
      (node (ref "C7") (pin "1") (pintype "passive"))
      (node (ref "C8") (pin "1") (pintype "passive"))
      (node (ref "CN1") (pin "1") (pinfunction "1_1") (pintype "passive"))
      (node (ref "D2") (pin "1") (pinfunction "K_1") (pintype "passive"))
      (node (ref "D3") (pin "1") (pinfunction "K_1") (pintype "passive"))
    )
    (net (code "45") (name "VCC2") (class "Default")
      (node (ref "C10") (pin "1") (pintype "passive"))
      (node (ref "C15") (pin "1") (pintype "passive"))
      (node (ref "C9") (pin "1") (pintype "passive"))
      (node (ref "CN5") (pin "1") (pinfunction "1_1") (pintype "passive"))
      (node (ref "L2") (pin "1") (pinfunction "1_1") (pintype "passive"))
      (node (ref "R6") (pin "2") (pinfunction "2_2") (pintype "passive"))
      (node (ref "U2") (pin "5") (pinfunction "VIN_5") (pintype "passive"))
    )
    (net (code "46") (name "VCC3") (class "Default")
      (node (ref "C11") (pin "1") (pintype "passive"))
      (node (ref "C12") (pin "1") (pintype "passive"))
      (node (ref "C13") (pin "1") (pintype "passive"))
      (node (ref "C14") (pin "1") (pintype "passive"))
      (node (ref "CN4") (pin "1") (pinfunction "1_1") (pintype "passive"))
      (node (ref "D4") (pin "1") (pinfunction "K_1") (pintype "passive"))
      (node (ref "D5") (pin "1") (pinfunction "K_1") (pintype "passive"))
      (node (ref "R5") (pin "2") (pinfunction "2_2") (pintype "passive"))
    )
    (net (code "47") (name "VCC4") (class "Default")
      (node (ref "CN14") (pin "1") (pinfunction "1_1") (pintype "passive"))
      (node (ref "R12") (pin "2") (pinfunction "2_2") (pintype "passive"))
    )
    (net (code "48") (name "VCC5") (class "Default")
      (node (ref "C33") (pin "1") (pintype "passive"))
      (node (ref "CN20") (pin "1") (pinfunction "1_1") (pintype "passive"))
      (node (ref "U8") (pin "3") (pinfunction "VIN_3") (pintype "passive"))
    )
    (net (code "49") (name "VSS") (class "Default")
      (node (ref "C27") (pin "1") (pintype "passive"))
      (node (ref "C31") (pin "1") (pintype "passive"))
      (node (ref "CN16") (pin "1") (pinfunction "1_1") (pintype "passive"))
      (node (ref "Q3") (pin "3") (pinfunction "D_3") (pintype "passive"))
      (node (ref "U7") (pin "2") (pinfunction "VSS_2") (pintype "power_in"))
    )
    (net (code "50") (name "unconnected-(U3-NC-Pad4)") (class "Default")
      (node (ref "U3") (pin "4") (pinfunction "NC_4") (pintype "passive+no_connect"))
    )
    (net (code "51") (name "unconnected-(U4-NC-Pad1)") (class "Default")
      (node (ref "U4") (pin "1") (pinfunction "NC_1") (pintype "passive"))
    )
  )
)
